# roomba_main_pcb_v1.net
KiCad netlist of a schematic drawn in EAGLE
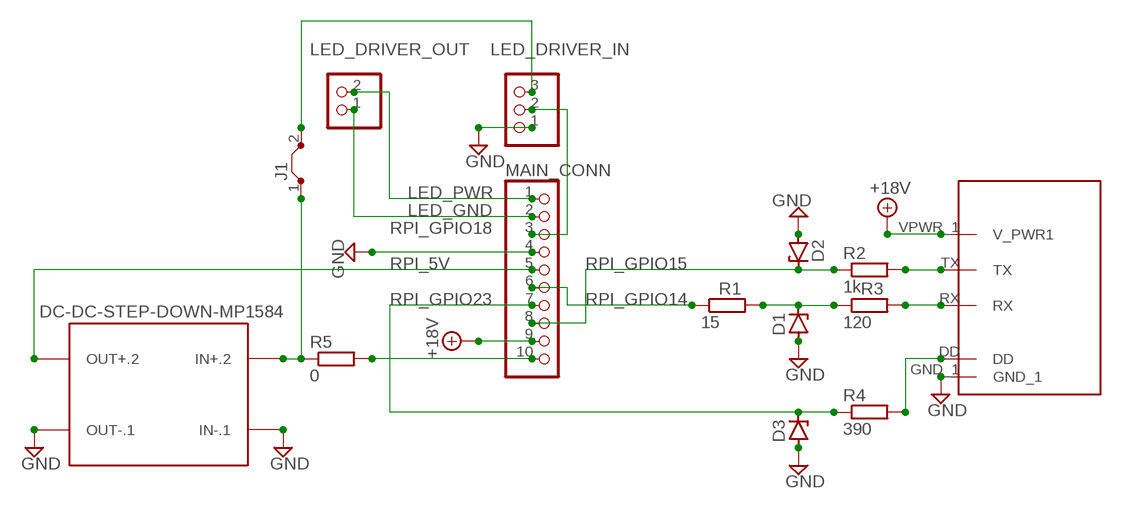
[diagram p0: schematic, sheet 1]

(export (version "E")
  (design (tool "Eeschema 10.0.6"))
  (components
    (comp (ref "D1")
      (value "ZENER-DIODESOD80C")
      (footprint "eagle-import:SOD80C")
      (libsource (lib "eagle-import") (part "ZENER-DIODESOD80C"))
    )
    (comp (ref "D2")
      (value "ZENER-DIODESOD80C")
      (footprint "eagle-import:SOD80C")
      (libsource (lib "eagle-import") (part "ZENER-DIODESOD80C"))
    )
    (comp (ref "D3")
      (value "ZENER-DIODESOD80C")
      (footprint "eagle-import:SOD80C")
      (libsource (lib "eagle-import") (part "ZENER-DIODESOD80C"))
    )
    (comp (ref "J1")
      (value "J25MM")
      (footprint "eagle-import:25")
      (libsource (lib "eagle-import") (part "J25MM"))
    )
    (comp (ref "LED_DRIVER_IN")
      (value "PINHD-1X3")
      (footprint "eagle-import:1X03")
      (libsource (lib "eagle-import") (part "PINHD-1X3"))
    )
    (comp (ref "LED_DRIVER_OUT")
      (value "PINHD-1X2")
      (footprint "eagle-import:1X02")
      (libsource (lib "eagle-import") (part "PINHD-1X2"))
    )
    (comp (ref "MAIN_CONN")
      (value "PINHD-1X10/90")
      (footprint "eagle-import:1X10_90")
      (libsource (lib "eagle-import") (part "PINHD-1X10/90"))
    )
    (comp (ref "R1")
      (value "15")
      (footprint "eagle-import:M1206")
      (libsource (lib "eagle-import") (part "R-EU_M1206"))
    )
    (comp (ref "R2")
      (value "1k")
      (footprint "eagle-import:M1206")
      (libsource (lib "eagle-import") (part "R-EU_M1206"))
    )
    (comp (ref "R3")
      (value "120")
      (footprint "eagle-import:M1206")
      (libsource (lib "eagle-import") (part "R-EU_M1206"))
    )
    (comp (ref "R4")
      (value "390")
      (footprint "eagle-import:M1206")
      (libsource (lib "eagle-import") (part "R-EU_M1206"))
    )
    (comp (ref "R5")
      (value "0")
      (footprint "eagle-import:M1206")
      (libsource (lib "eagle-import") (part "R-EU_M1206"))
    )
    (comp (ref "ROOMBA_PORT")
      (value "7_PIN")
      (footprint "eagle-import:PIN-7")
      (libsource (lib "eagle-import") (part "7_PIN"))
    )
    (comp (ref "U$1")
      (value "DC-DC-STEP-DOWN-MP1584")
      (footprint "eagle-import:DC-DC-STEP-DOWN-MP1584")
      (libsource (lib "eagle-import") (part "DC-DC-STEP-DOWN-MP1584"))
    )
  )
  (nets
    (net (code "1") (name "+18V") (class "Default")
      (node (ref "MAIN_CONN") (pin "9") (pinfunction "9_9") (pintype "passive"))
      (node (ref "ROOMBA_PORT") (pin "VPWR_1") (pinfunction "V_PWR1_VPWR_1") (pintype "bidirectional"))
    )
    (net (code "2") (name "/LED_GND") (class "Default")
      (node (ref "LED_DRIVER_OUT") (pin "1") (pinfunction "1_1") (pintype "passive"))
      (node (ref "MAIN_CONN") (pin "2") (pinfunction "2_2") (pintype "passive"))
    )
    (net (code "3") (name "/LED_PWR") (class "Default")
      (node (ref "LED_DRIVER_OUT") (pin "2") (pinfunction "2_2") (pintype "passive"))
      (node (ref "MAIN_CONN") (pin "1") (pinfunction "1_1") (pintype "passive"))
    )
    (net (code "4") (name "/RPI_5V") (class "Default")
      (node (ref "MAIN_CONN") (pin "5") (pinfunction "5_5") (pintype "passive"))
      (node (ref "U$1") (pin "OUT+.2") (pinfunction "OUT+.2_OUT+.2") (pintype "bidirectional"))
    )
    (net (code "5") (name "/RPI_GPIO14") (class "Default")
      (node (ref "MAIN_CONN") (pin "6") (pinfunction "6_6") (pintype "passive"))
      (node (ref "R1") (pin "1") (pinfunction "1_1") (pintype "passive"))
    )
    (net (code "6") (name "/RPI_GPIO15") (class "Default")
      (node (ref "D2") (pin "C") (pinfunction "C_C") (pintype "passive"))
      (node (ref "MAIN_CONN") (pin "8") (pinfunction "8_8") (pintype "passive"))
      (node (ref "R2") (pin "1") (pinfunction "1_1") (pintype "passive"))
    )
    (net (code "7") (name "/RPI_GPIO18") (class "Default")
      (node (ref "LED_DRIVER_IN") (pin "2") (pinfunction "2_2") (pintype "passive"))
      (node (ref "MAIN_CONN") (pin "3") (pinfunction "3_3") (pintype "passive"))
    )
    (net (code "8") (name "/RPI_GPIO23") (class "Default")
      (node (ref "D3") (pin "C") (pinfunction "C_C") (pintype "passive"))
      (node (ref "MAIN_CONN") (pin "7") (pinfunction "7_7") (pintype "passive"))
      (node (ref "R4") (pin "1") (pinfunction "1_1") (pintype "passive"))
    )
    (net (code "9") (name "GND") (class "Default")
      (node (ref "D1") (pin "A") (pinfunction "A_A") (pintype "passive"))
      (node (ref "D2") (pin "A") (pinfunction "A_A") (pintype "passive"))
      (node (ref "D3") (pin "A") (pinfunction "A_A") (pintype "passive"))
      (node (ref "LED_DRIVER_IN") (pin "1") (pinfunction "1_1") (pintype "passive"))
      (node (ref "MAIN_CONN") (pin "4") (pinfunction "4_4") (pintype "passive"))
      (node (ref "ROOMBA_PORT") (pin "GND_1") (pinfunction "GND_1_GND_1") (pintype "bidirectional"))
      (node (ref "U$1") (pin "IN-.1") (pinfunction "IN-.1_IN-.1") (pintype "bidirectional"))
      (node (ref "U$1") (pin "OUT-.1") (pinfunction "OUT-.1_OUT-.1") (pintype "bidirectional"))
    )
    (net (code "10") (name "Net-(D1-PadC)") (class "Default")
      (node (ref "D1") (pin "C") (pinfunction "C_C") (pintype "passive"))
      (node (ref "R1") (pin "2") (pinfunction "2_2") (pintype "passive"))
      (node (ref "R3") (pin "1") (pinfunction "1_1") (pintype "passive"))
    )
    (net (code "11") (name "Net-(J1-Pad1)") (class "Default")
      (node (ref "J1") (pin "1") (pinfunction "1_1") (pintype "passive"))
      (node (ref "R5") (pin "1") (pinfunction "1_1") (pintype "passive"))
      (node (ref "U$1") (pin "IN+.2") (pinfunction "IN+.2_IN+.2") (pintype "bidirectional"))
    )
    (net (code "12") (name "Net-(J1-Pad2)") (class "Default")
      (node (ref "J1") (pin "2") (pinfunction "2_2") (pintype "passive"))
      (node (ref "LED_DRIVER_IN") (pin "3") (pinfunction "3_3") (pintype "passive"))
    )
    (net (code "13") (name "Net-(MAIN_CONN-Pad10)") (class "Default")
      (node (ref "MAIN_CONN") (pin "10") (pinfunction "10_10") (pintype "passive"))
      (node (ref "R5") (pin "2") (pinfunction "2_2") (pintype "passive"))
    )
    (net (code "14") (name "Net-(R2-Pad2)") (class "Default")
      (node (ref "R2") (pin "2") (pinfunction "2_2") (pintype "passive"))
      (node (ref "ROOMBA_PORT") (pin "TX") (pinfunction "TX_TX") (pintype "bidirectional"))
    )
    (net (code "15") (name "Net-(R3-Pad2)") (class "Default")
      (node (ref "R3") (pin "2") (pinfunction "2_2") (pintype "passive"))
      (node (ref "ROOMBA_PORT") (pin "RX") (pinfunction "RX_RX") (pintype "bidirectional"))
    )
    (net (code "16") (name "Net-(R4-Pad2)") (class "Default")
      (node (ref "R4") (pin "2") (pinfunction "2_2") (pintype "passive"))
      (node (ref "ROOMBA_PORT") (pin "DD") (pinfunction "DD_DD") (pintype "bidirectional"))
    )
  )
)
